# SCH_Emon.net
KiCad netlist of a schematic drawn in EasyEDA
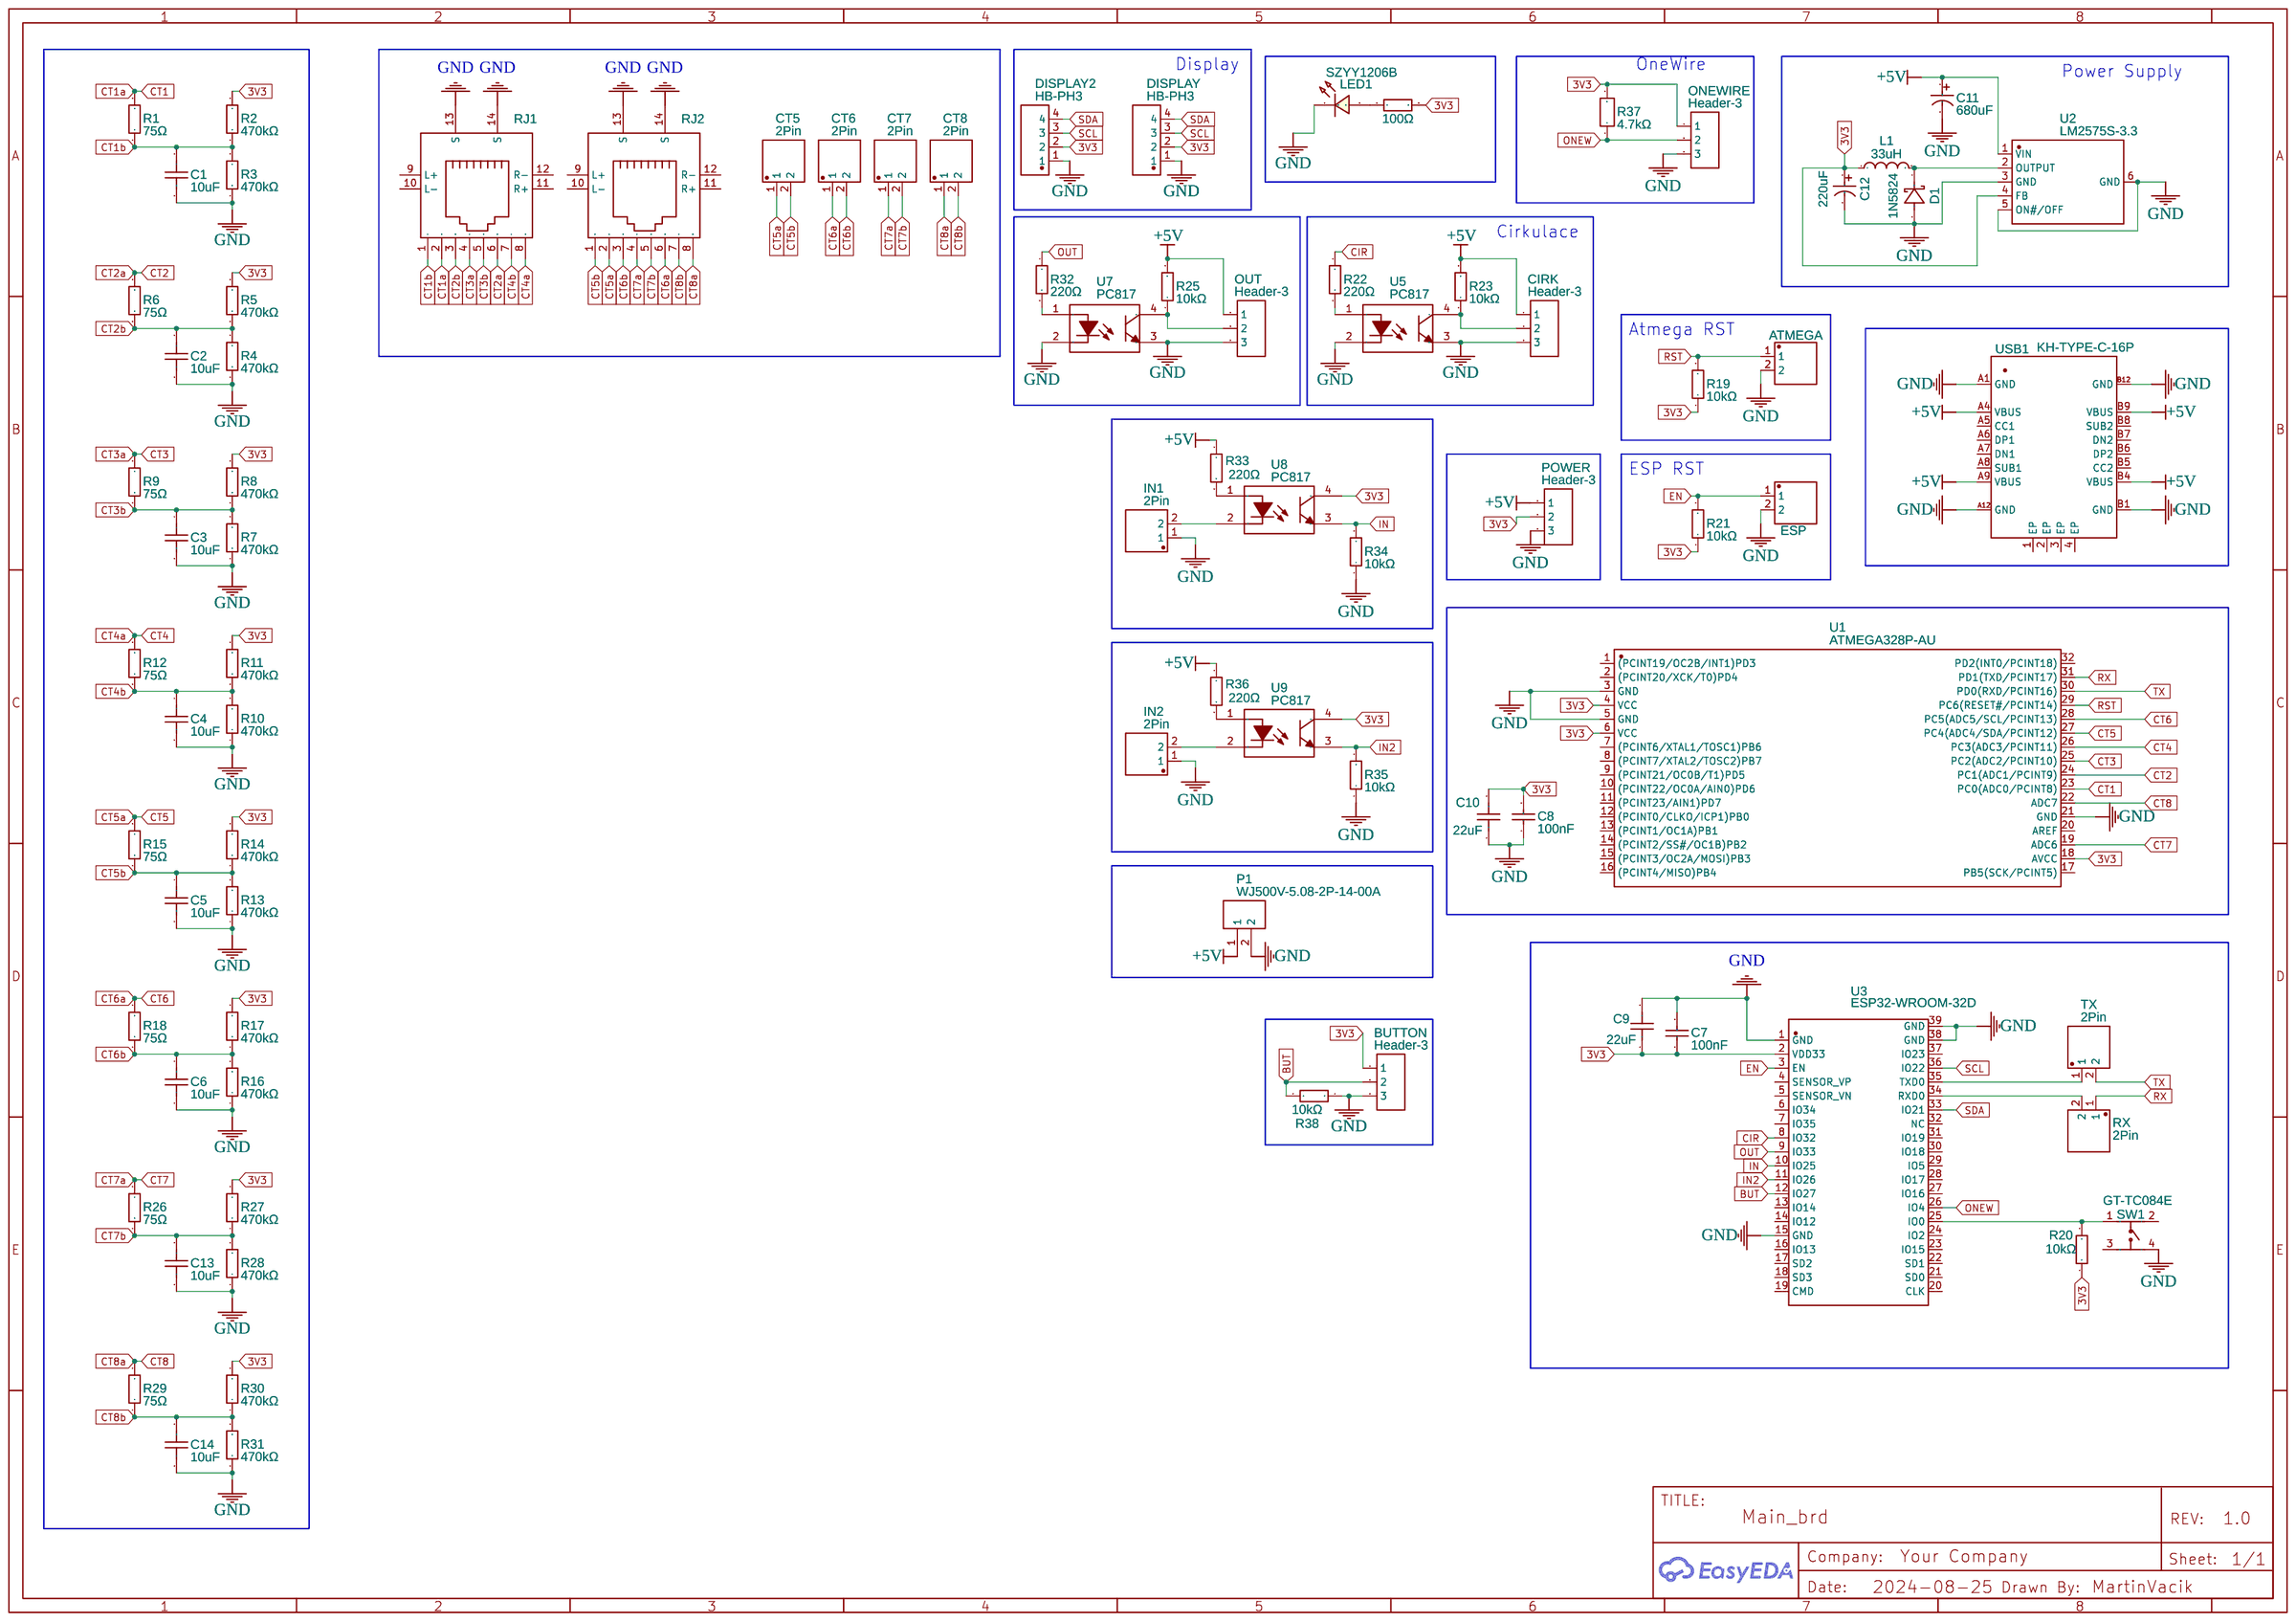
[diagram p0: schematic sheet]

(export (version "E")
  (design (tool "Eeschema 10.0.6"))
  (components
    (comp (ref "ATMEGA")
      (value "Atmega")
      (fields (field (name "Manufacturer Part") "B-2100S02P-A110") (field (name "Manufacturer") "Ckmtw(灿科盟)"))
      (libsource (lib "") (part "210S-1*2P L=11.6MMGold-plated black_2"))
    )
    (comp (ref "BUTTON")
      (value "Header-3")
      (fields (field (name "Manufacturer Part") "2.54-1*3P针") (field (name "Manufacturer") "BOOMELE(博穆精密)"))
      (libsource (lib "") (part "Header-Male-2.54_1x3_4"))
    )
    (comp (ref "C1")
      (value "10uF")
      (fields (field (name "Manufacturer Part") "1206B106K100NT") (field (name "Manufacturer") "FH(风华)"))
      (libsource (lib "") (part "1206B106K100NT"))
    )
    (comp (ref "C2")
      (value "10uF")
      (fields (field (name "Manufacturer Part") "1206B106K100NT") (field (name "Manufacturer") "FH(风华)"))
      (libsource (lib "") (part "1206B106K100NT"))
    )
    (comp (ref "C3")
      (value "10uF")
      (fields (field (name "Manufacturer Part") "1206B106K100NT") (field (name "Manufacturer") "FH(风华)"))
      (libsource (lib "") (part "1206B106K100NT"))
    )
    (comp (ref "C4")
      (value "10uF")
      (fields (field (name "Manufacturer Part") "1206B106K100NT") (field (name "Manufacturer") "FH(风华)"))
      (libsource (lib "") (part "1206B106K100NT"))
    )
    (comp (ref "C5")
      (value "10uF")
      (fields (field (name "Manufacturer Part") "1206B106K100NT") (field (name "Manufacturer") "FH(风华)"))
      (libsource (lib "") (part "1206B106K100NT"))
    )
    (comp (ref "C6")
      (value "10uF")
      (fields (field (name "Manufacturer Part") "1206B106K100NT") (field (name "Manufacturer") "FH(风华)"))
      (libsource (lib "") (part "1206B106K100NT"))
    )
    (comp (ref "C7")
      (value "100nF")
      (fields (field (name "Manufacturer Part") "1206B104K500NT") (field (name "Manufacturer") "FH(风华)"))
      (libsource (lib "") (part "1206B104K500NT"))
    )
    (comp (ref "C8")
      (value "100nF")
      (fields (field (name "Manufacturer Part") "1206B104K500NT") (field (name "Manufacturer") "FH(风华)"))
      (libsource (lib "") (part "1206B104K500NT"))
    )
    (comp (ref "C9")
      (value "22uF")
      (fields
        (field (name "Manufacturer Part") "CL31A226KOHNNNE")
        (field (name "Manufacturer") "SAMSUNG(三星)")
      )
      (libsource (lib "") (part "CL31A226KOHNNNE"))
    )
    (comp (ref "C10")
      (value "22uF")
      (fields
        (field (name "Manufacturer Part") "CL31A226KOHNNNE")
        (field (name "Manufacturer") "SAMSUNG(三星)")
      )
      (libsource (lib "") (part "CL31A226KOHNNNE"))
    )
    (comp (ref "C11")
      (value "680uF")
      (fields
        (field (name "Manufacturer Part") "GR687M025G17RR0VL4FP0")
        (field (name "Manufacturer") "CX(承兴)")
      )
      (libsource (lib "") (part "680uF 25V"))
    )
    (comp (ref "C12")
      (value "220uF")
      (fields
        (field (name "Manufacturer Part") "ZF227M016E07RR0VH4FP0")
        (field (name "Manufacturer") "CX(承兴)")
      )
      (libsource (lib "") (part "220uF 16V Black high frequency"))
    )
    (comp (ref "C13")
      (value "10uF")
      (fields (field (name "Manufacturer Part") "1206B106K100NT") (field (name "Manufacturer") "FH(风华)"))
      (libsource (lib "") (part "1206B106K100NT"))
    )
    (comp (ref "C14")
      (value "10uF")
      (fields (field (name "Manufacturer Part") "1206B106K100NT") (field (name "Manufacturer") "FH(风华)"))
      (libsource (lib "") (part "1206B106K100NT"))
    )
    (comp (ref "CIRK")
      (value "Header-3")
      (fields (field (name "Manufacturer Part") "2.54-1*3P针") (field (name "Manufacturer") "BOOMELE(博穆精密)"))
      (libsource (lib "") (part "Header-Male-2.54_1x3_3"))
    )
    (comp (ref "CT5")
      (value "2Pin")
      (fields (field (name "Manufacturer Part") "B-2100S02P-A110") (field (name "Manufacturer") "Ckmtw(灿科盟)"))
      (libsource (lib "") (part "210S-1*2P L=11.6MMGold-plated black_4"))
    )
    (comp (ref "CT6")
      (value "2Pin")
      (fields (field (name "Manufacturer Part") "B-2100S02P-A110") (field (name "Manufacturer") "Ckmtw(灿科盟)"))
      (libsource (lib "") (part "210S-1*2P L=11.6MMGold-plated black_4"))
    )
    (comp (ref "CT7")
      (value "2Pin")
      (fields (field (name "Manufacturer Part") "B-2100S02P-A110") (field (name "Manufacturer") "Ckmtw(灿科盟)"))
      (libsource (lib "") (part "210S-1*2P L=11.6MMGold-plated black_4"))
    )
    (comp (ref "CT8")
      (value "2Pin")
      (fields (field (name "Manufacturer Part") "B-2100S02P-A110") (field (name "Manufacturer") "Ckmtw(灿科盟)"))
      (libsource (lib "") (part "210S-1*2P L=11.6MMGold-plated black_4"))
    )
    (comp (ref "D1")
      (value "1N5824")
      (fields (field (name "Manufacturer") "FUXINSEMI(富芯森美)"))
      (libsource (lib "") (part "1N5824_C7503125"))
    )
    (comp (ref "DISPLAY")
      (value "HB-PH3")
      (fields
        (field (name "Manufacturer Part") "HB-PH3-25414PB2GOP")
        (field (name "Manufacturer") "HANBO(汉博)")
      )
      (libsource (lib "") (part "HB-PH3-25414PB2GOP"))
    )
    (comp (ref "DISPLAY2")
      (value "HB-PH3")
      (fields
        (field (name "Manufacturer Part") "HB-PH3-25414PB2GOP")
        (field (name "Manufacturer") "HANBO(汉博)")
      )
      (libsource (lib "") (part "HB-PH3-25414PB2GOP"))
    )
    (comp (ref "ESP")
      (value "ESP")
      (fields (field (name "Manufacturer Part") "B-2100S02P-A110") (field (name "Manufacturer") "Ckmtw(灿科盟)"))
      (libsource (lib "") (part "210S-1*2P L=11.6MMGold-plated black_3"))
    )
    (comp (ref "IN1")
      (value "2Pin")
      (fields (field (name "Manufacturer Part") "B-2100S02P-A110") (field (name "Manufacturer") "Ckmtw(灿科盟)"))
      (libsource (lib "") (part "210S-1*2P L=11.6MMGold-plated black_1"))
    )
    (comp (ref "IN2")
      (value "2Pin")
      (fields (field (name "Manufacturer Part") "B-2100S02P-A110") (field (name "Manufacturer") "Ckmtw(灿科盟)"))
      (libsource (lib "") (part "210S-1*2P L=11.6MMGold-plated black_1"))
    )
    (comp (ref "L1")
      (value "33uH")
      (fields (field (name "Manufacturer Part") "FXL0650-330-M") (field (name "Manufacturer") "cjiang(长江微电)"))
      (libsource (lib "") (part "FXL0650-330-M"))
    )
    (comp (ref "LED1")
      (value "SZYY1206B")
      (fields (field (name "Manufacturer") "yongyu(永裕光电)"))
      (libsource (lib "") (part "SZYY1206B"))
    )
    (comp (ref "ONEWIRE")
      (value "Header-3")
      (fields (field (name "Manufacturer Part") "2.54-1*3P针") (field (name "Manufacturer") "BOOMELE(博穆精密)"))
      (libsource (lib "") (part "Header-Male-2.54_1x3_1"))
    )
    (comp (ref "OUT")
      (value "Header-3")
      (fields (field (name "Manufacturer Part") "2.54-1*3P针") (field (name "Manufacturer") "BOOMELE(博穆精密)"))
      (libsource (lib "") (part "Header-Male-2.54_1x3"))
    )
    (comp (ref "P1")
      (value "WJ500V-5.08-2P-14-00A")
      (fields
        (field (name "Manufacturer Part") "WJ500V-5.08-2P")
        (field (name "Manufacturer") "KANGNEX(康奈克斯电气)")
      )
      (libsource (lib "") (part "WJ500V-5.08-2P-14-00A"))
    )
    (comp (ref "POWER")
      (value "Header-3")
      (fields (field (name "Manufacturer Part") "2.54-1*3P针") (field (name "Manufacturer") "BOOMELE(博穆精密)"))
      (libsource (lib "") (part "Header-Male-2.54_1x3_2"))
    )
    (comp (ref "R1")
      (value "75Ω")
      (fields
        (field (name "Manufacturer Part") "1206W4J0750T5E")
        (field (name "Manufacturer") "UNI-ROYAL(厚声)")
      )
      (libsource (lib "") (part "1206W4J0750T5E"))
    )
    (comp (ref "R2")
      (value "470kΩ")
      (fields
        (field (name "Manufacturer Part") "1206W4F4703T5E")
        (field (name "Manufacturer") "UNI-ROYAL(厚声)")
      )
      (libsource (lib "") (part "1206W4F4703T5E"))
    )
    (comp (ref "R3")
      (value "470kΩ")
      (fields
        (field (name "Manufacturer Part") "1206W4F4703T5E")
        (field (name "Manufacturer") "UNI-ROYAL(厚声)")
      )
      (libsource (lib "") (part "1206W4F4703T5E"))
    )
    (comp (ref "R4")
      (value "470kΩ")
      (fields
        (field (name "Manufacturer Part") "1206W4F4703T5E")
        (field (name "Manufacturer") "UNI-ROYAL(厚声)")
      )
      (libsource (lib "") (part "1206W4F4703T5E"))
    )
    (comp (ref "R5")
      (value "470kΩ")
      (fields
        (field (name "Manufacturer Part") "1206W4F4703T5E")
        (field (name "Manufacturer") "UNI-ROYAL(厚声)")
      )
      (libsource (lib "") (part "1206W4F4703T5E"))
    )
    (comp (ref "R6")
      (value "75Ω")
      (fields
        (field (name "Manufacturer Part") "1206W4J0750T5E")
        (field (name "Manufacturer") "UNI-ROYAL(厚声)")
      )
      (libsource (lib "") (part "1206W4J0750T5E"))
    )
    (comp (ref "R7")
      (value "470kΩ")
      (fields
        (field (name "Manufacturer Part") "1206W4F4703T5E")
        (field (name "Manufacturer") "UNI-ROYAL(厚声)")
      )
      (libsource (lib "") (part "1206W4F4703T5E"))
    )
    (comp (ref "R8")
      (value "470kΩ")
      (fields
        (field (name "Manufacturer Part") "1206W4F4703T5E")
        (field (name "Manufacturer") "UNI-ROYAL(厚声)")
      )
      (libsource (lib "") (part "1206W4F4703T5E"))
    )
    (comp (ref "R9")
      (value "75Ω")
      (fields
        (field (name "Manufacturer Part") "1206W4J0750T5E")
        (field (name "Manufacturer") "UNI-ROYAL(厚声)")
      )
      (libsource (lib "") (part "1206W4J0750T5E"))
    )
    (comp (ref "R10")
      (value "470kΩ")
      (fields
        (field (name "Manufacturer Part") "1206W4F4703T5E")
        (field (name "Manufacturer") "UNI-ROYAL(厚声)")
      )
      (libsource (lib "") (part "1206W4F4703T5E"))
    )
    (comp (ref "R11")
      (value "470kΩ")
      (fields
        (field (name "Manufacturer Part") "1206W4F4703T5E")
        (field (name "Manufacturer") "UNI-ROYAL(厚声)")
      )
      (libsource (lib "") (part "1206W4F4703T5E"))
    )
    (comp (ref "R12")
      (value "75Ω")
      (fields
        (field (name "Manufacturer Part") "1206W4J0750T5E")
        (field (name "Manufacturer") "UNI-ROYAL(厚声)")
      )
      (libsource (lib "") (part "1206W4J0750T5E"))
    )
    (comp (ref "R13")
      (value "470kΩ")
      (fields
        (field (name "Manufacturer Part") "1206W4F4703T5E")
        (field (name "Manufacturer") "UNI-ROYAL(厚声)")
      )
      (libsource (lib "") (part "1206W4F4703T5E"))
    )
    (comp (ref "R14")
      (value "470kΩ")
      (fields
        (field (name "Manufacturer Part") "1206W4F4703T5E")
        (field (name "Manufacturer") "UNI-ROYAL(厚声)")
      )
      (libsource (lib "") (part "1206W4F4703T5E"))
    )
    (comp (ref "R15")
      (value "75Ω")
      (fields
        (field (name "Manufacturer Part") "1206W4J0750T5E")
        (field (name "Manufacturer") "UNI-ROYAL(厚声)")
      )
      (libsource (lib "") (part "1206W4J0750T5E"))
    )
    (comp (ref "R16")
      (value "470kΩ")
      (fields
        (field (name "Manufacturer Part") "1206W4F4703T5E")
        (field (name "Manufacturer") "UNI-ROYAL(厚声)")
      )
      (libsource (lib "") (part "1206W4F4703T5E"))
    )
    (comp (ref "R17")
      (value "470kΩ")
      (fields
        (field (name "Manufacturer Part") "1206W4F4703T5E")
        (field (name "Manufacturer") "UNI-ROYAL(厚声)")
      )
      (libsource (lib "") (part "1206W4F4703T5E"))
    )
    (comp (ref "R18")
      (value "75Ω")
      (fields
        (field (name "Manufacturer Part") "1206W4J0750T5E")
        (field (name "Manufacturer") "UNI-ROYAL(厚声)")
      )
      (libsource (lib "") (part "1206W4J0750T5E"))
    )
    (comp (ref "R19")
      (value "10kΩ")
      (fields
        (field (name "Manufacturer Part") "1206W4F1002T5E")
        (field (name "Manufacturer") "UNI-ROYAL(厚声)")
      )
      (libsource (lib "") (part "1206W4F1002T5E"))
    )
    (comp (ref "R20")
      (value "10kΩ")
      (fields
        (field (name "Manufacturer Part") "1206W4F1002T5E")
        (field (name "Manufacturer") "UNI-ROYAL(厚声)")
      )
      (libsource (lib "") (part "1206W4F1002T5E"))
    )
    (comp (ref "R21")
      (value "10kΩ")
      (fields
        (field (name "Manufacturer Part") "1206W4F1002T5E")
        (field (name "Manufacturer") "UNI-ROYAL(厚声)")
      )
      (libsource (lib "") (part "1206W4F1002T5E"))
    )
    (comp (ref "R22")
      (value "220Ω")
      (fields
        (field (name "Manufacturer Part") "1206W4J0221T5E")
        (field (name "Manufacturer") "UNI-ROYAL(厚声)")
      )
      (libsource (lib "") (part "1206W4J0221T5E"))
    )
    (comp (ref "R23")
      (value "10kΩ")
      (fields
        (field (name "Manufacturer Part") "1206W4F1002T5E")
        (field (name "Manufacturer") "UNI-ROYAL(厚声)")
      )
      (libsource (lib "") (part "1206W4F1002T5E"))
    )
    (comp (ref "R24")
      (value "100Ω")
      (fields
        (field (name "Manufacturer Part") "1206W4F1000T5E")
        (field (name "Manufacturer") "UNI-ROYAL(厚声)")
      )
      (libsource (lib "") (part "1206W4F1000T5E"))
    )
    (comp (ref "R25")
      (value "10kΩ")
      (fields
        (field (name "Manufacturer Part") "1206W4F1002T5E")
        (field (name "Manufacturer") "UNI-ROYAL(厚声)")
      )
      (libsource (lib "") (part "1206W4F1002T5E"))
    )
    (comp (ref "R26")
      (value "75Ω")
      (fields
        (field (name "Manufacturer Part") "1206W4J0750T5E")
        (field (name "Manufacturer") "UNI-ROYAL(厚声)")
      )
      (libsource (lib "") (part "1206W4J0750T5E"))
    )
    (comp (ref "R27")
      (value "470kΩ")
      (fields
        (field (name "Manufacturer Part") "1206W4F4703T5E")
        (field (name "Manufacturer") "UNI-ROYAL(厚声)")
      )
      (libsource (lib "") (part "1206W4F4703T5E"))
    )
    (comp (ref "R28")
      (value "470kΩ")
      (fields
        (field (name "Manufacturer Part") "1206W4F4703T5E")
        (field (name "Manufacturer") "UNI-ROYAL(厚声)")
      )
      (libsource (lib "") (part "1206W4F4703T5E"))
    )
    (comp (ref "R29")
      (value "75Ω")
      (fields
        (field (name "Manufacturer Part") "1206W4J0750T5E")
        (field (name "Manufacturer") "UNI-ROYAL(厚声)")
      )
      (libsource (lib "") (part "1206W4J0750T5E"))
    )
    (comp (ref "R30")
      (value "470kΩ")
      (fields
        (field (name "Manufacturer Part") "1206W4F4703T5E")
        (field (name "Manufacturer") "UNI-ROYAL(厚声)")
      )
      (libsource (lib "") (part "1206W4F4703T5E"))
    )
    (comp (ref "R31")
      (value "470kΩ")
      (fields
        (field (name "Manufacturer Part") "1206W4F4703T5E")
        (field (name "Manufacturer") "UNI-ROYAL(厚声)")
      )
      (libsource (lib "") (part "1206W4F4703T5E"))
    )
    (comp (ref "R32")
      (value "220Ω")
      (fields
        (field (name "Manufacturer Part") "1206W4J0221T5E")
        (field (name "Manufacturer") "UNI-ROYAL(厚声)")
      )
      (libsource (lib "") (part "1206W4J0221T5E"))
    )
    (comp (ref "R33")
      (value "220Ω")
      (fields
        (field (name "Manufacturer Part") "1206W4J0221T5E")
        (field (name "Manufacturer") "UNI-ROYAL(厚声)")
      )
      (libsource (lib "") (part "1206W4J0221T5E"))
    )
    (comp (ref "R34")
      (value "10kΩ")
      (fields
        (field (name "Manufacturer Part") "1206W4F1002T5E")
        (field (name "Manufacturer") "UNI-ROYAL(厚声)")
      )
      (libsource (lib "") (part "1206W4F1002T5E"))
    )
    (comp (ref "R35")
      (value "10kΩ")
      (fields
        (field (name "Manufacturer Part") "1206W4F1002T5E")
        (field (name "Manufacturer") "UNI-ROYAL(厚声)")
      )
      (libsource (lib "") (part "1206W4F1002T5E"))
    )
    (comp (ref "R36")
      (value "220Ω")
      (fields
        (field (name "Manufacturer Part") "1206W4J0221T5E")
        (field (name "Manufacturer") "UNI-ROYAL(厚声)")
      )
      (libsource (lib "") (part "1206W4J0221T5E"))
    )
    (comp (ref "R37")
      (value "4.7kΩ")
      (fields (field (name "Manufacturer Part") "FRC1206J472 TS") (field (name "Manufacturer") "FOJAN(富捷)"))
      (libsource (lib "") (part "FRC1206J472 TS"))
    )
    (comp (ref "R38")
      (value "10kΩ")
      (fields
        (field (name "Manufacturer Part") "1206W4F1002T5E")
        (field (name "Manufacturer") "UNI-ROYAL(厚声)")
      )
      (libsource (lib "") (part "1206W4F1002T5E_1"))
    )
    (comp (ref "RJ1")
      (value "R-RJ45R08P-C000")
      (fields (field (name "Manufacturer") "Ckmtw(灿科盟)"))
      (libsource (lib "") (part "R-RJ45R08P-C000"))
    )
    (comp (ref "RJ2")
      (value "R-RJ45R08P-C000")
      (fields (field (name "Manufacturer") "Ckmtw(灿科盟)"))
      (libsource (lib "") (part "R-RJ45R08P-C000"))
    )
    (comp (ref "RX")
      (value "2Pin")
      (fields (field (name "Manufacturer Part") "B-2100S02P-A110") (field (name "Manufacturer") "Ckmtw(灿科盟)"))
      (libsource (lib "") (part "210S-1*2P L=11.6MMGold-plated black_5"))
    )
    (comp (ref "SW1")
      (value "GT-TC084E")
      (fields
        (field (name "Manufacturer Part") "GT-TC084E-H017-L5")
        (field (name "Manufacturer") "G-Switch(品赞)")
      )
      (libsource (lib "") (part "GT-TC084E-H017-L5"))
    )
    (comp (ref "TX")
      (value "2Pin")
      (fields (field (name "Manufacturer Part") "B-2100S02P-A110") (field (name "Manufacturer") "Ckmtw(灿科盟)"))
      (libsource (lib "") (part "210S-1*2P L=11.6MMGold-plated black"))
    )
    (comp (ref "U1")
      (value "ATMEGA328P-AU")
      (fields (field (name "Manufacturer") "MICROCHIP(美国微芯)"))
      (libsource (lib "") (part "ATMEGA328P-AU"))
    )
    (comp (ref "U2")
      (value "LM2575S-3.3")
      (fields (field (name "Manufacturer") "UMW(友台半导体)"))
      (libsource (lib "") (part "LM2575S-3.3_C347404"))
    )
    (comp (ref "U3")
      (value "ESP32-WROOM-32D")
      (fields
        (field (name "Manufacturer Part") "ESP32-WROOM-32D-N4")
        (field (name "Manufacturer") "ESPRESSIF(乐鑫)")
      )
      (libsource (lib "") (part "ESP32-WROOM-32D"))
    )
    (comp (ref "U5")
      (value "PC817")
      (fields (field (name "Manufacturer Part") "PC817X2CSP9F") (field (name "Manufacturer") "SHARP(夏普)"))
      (libsource (lib "") (part "PC817X2CSP9F"))
    )
    (comp (ref "U7")
      (value "PC817")
      (fields (field (name "Manufacturer Part") "PC817X2CSP9F") (field (name "Manufacturer") "SHARP(夏普)"))
      (libsource (lib "") (part "PC817X2CSP9F"))
    )
    (comp (ref "U8")
      (value "PC817")
      (fields (field (name "Manufacturer Part") "PC817X2CSP9F") (field (name "Manufacturer") "SHARP(夏普)"))
      (libsource (lib "") (part "PC817X2CSP9F"))
    )
    (comp (ref "U9")
      (value "PC817")
      (fields (field (name "Manufacturer Part") "PC817X2CSP9F") (field (name "Manufacturer") "SHARP(夏普)"))
      (libsource (lib "") (part "PC817X2CSP9F"))
    )
    (comp (ref "USB1")
      (value "KH-TYPE-C-16P")
      (fields (field (name "Manufacturer") "kinghelm(金航标)"))
      (libsource (lib "") (part "KH-TYPE-C-16P"))
    )
  )
  (nets
    (net (code "1") (name "+5V") (class "Default")
      (node (ref "C11") (pin "1") (pinfunction "1_1") (pintype "input"))
      (node (ref "CIRK") (pin "1") (pinfunction "1_1") (pintype "input"))
      (node (ref "OUT") (pin "1") (pinfunction "1_1") (pintype "input"))
      (node (ref "P1") (pin "1") (pinfunction "1_1") (pintype "unspecified"))
      (node (ref "POWER") (pin "1") (pinfunction "1_1") (pintype "input"))
      (node (ref "R23") (pin "2") (pinfunction "2_2") (pintype "input"))
      (node (ref "R25") (pin "2") (pinfunction "2_2") (pintype "input"))
      (node (ref "R33") (pin "1") (pinfunction "1_1") (pintype "input"))
      (node (ref "R36") (pin "1") (pinfunction "1_1") (pintype "input"))
      (node (ref "U2") (pin "1") (pinfunction "VIN_1") (pintype "unspecified"))
      (node (ref "USB1") (pin "A4") (pinfunction "VBUS_A4") (pintype "unspecified"))
      (node (ref "USB1") (pin "A9") (pinfunction "VBUS_A9") (pintype "unspecified"))
      (node (ref "USB1") (pin "B4") (pinfunction "VBUS_B4") (pintype "unspecified"))
      (node (ref "USB1") (pin "B9") (pinfunction "VBUS_B9") (pintype "unspecified"))
    )
    (net (code "2") (name "3V3") (class "Default")
      (node (ref "BUTTON") (pin "1") (pinfunction "1_1") (pintype "input"))
      (node (ref "C10") (pin "2") (pinfunction "2_2") (pintype "unspecified"))
      (node (ref "C12") (pin "1") (pinfunction "1_1") (pintype "input"))
      (node (ref "C7") (pin "1") (pinfunction "1_1") (pintype "input"))
      (node (ref "C8") (pin "2") (pinfunction "2_2") (pintype "input"))
      (node (ref "C9") (pin "1") (pinfunction "1_1") (pintype "unspecified"))
      (node (ref "DISPLAY") (pin "2") (pinfunction "2_2") (pintype "unspecified"))
      (node (ref "DISPLAY2") (pin "2") (pinfunction "2_2") (pintype "unspecified"))
      (node (ref "L1") (pin "1") (pinfunction "1_1") (pintype "unspecified"))
      (node (ref "ONEWIRE") (pin "1") (pinfunction "1_1") (pintype "input"))
      (node (ref "POWER") (pin "2") (pinfunction "2_2") (pintype "input"))
      (node (ref "R11") (pin "2") (pinfunction "2_2") (pintype "input"))
      (node (ref "R14") (pin "2") (pinfunction "2_2") (pintype "input"))
      (node (ref "R17") (pin "2") (pinfunction "2_2") (pintype "input"))
      (node (ref "R19") (pin "1") (pinfunction "1_1") (pintype "input"))
      (node (ref "R2") (pin "2") (pinfunction "2_2") (pintype "input"))
      (node (ref "R20") (pin "1") (pinfunction "1_1") (pintype "input"))
      (node (ref "R21") (pin "1") (pinfunction "1_1") (pintype "input"))
      (node (ref "R24") (pin "2") (pinfunction "2_2") (pintype "input"))
      (node (ref "R27") (pin "2") (pinfunction "2_2") (pintype "input"))
      (node (ref "R30") (pin "2") (pinfunction "2_2") (pintype "input"))
      (node (ref "R37") (pin "2") (pinfunction "2_2") (pintype "unspecified"))
      (node (ref "R5") (pin "2") (pinfunction "2_2") (pintype "input"))
      (node (ref "R8") (pin "2") (pinfunction "2_2") (pintype "input"))
      (node (ref "U1") (pin "18") (pinfunction "AVCC_18") (pintype "unspecified"))
      (node (ref "U1") (pin "4") (pinfunction "VCC_4") (pintype "unspecified"))
      (node (ref "U1") (pin "6") (pinfunction "VCC_6") (pintype "unspecified"))
      (node (ref "U2") (pin "4") (pinfunction "FB_4") (pintype "unspecified"))
      (node (ref "U3") (pin "2") (pinfunction "VDD33_2") (pintype "unspecified"))
      (node (ref "U8") (pin "4") (pinfunction "4_4") (pintype "unspecified"))
      (node (ref "U9") (pin "4") (pinfunction "4_4") (pintype "unspecified"))
    )
    (net (code "3") (name "BUT") (class "Default")
      (node (ref "BUTTON") (pin "2") (pinfunction "2_2") (pintype "input"))
      (node (ref "R38") (pin "2") (pinfunction "2_2") (pintype "input"))
      (node (ref "U3") (pin "12") (pinfunction "IO27_12") (pintype "unspecified"))
    )
    (net (code "4") (name "CIR") (class "Default")
      (node (ref "R22") (pin "1") (pinfunction "1_1") (pintype "input"))
      (node (ref "U3") (pin "8") (pinfunction "IO32_8") (pintype "unspecified"))
    )
    (net (code "5") (name "CT1") (class "Default")
      (node (ref "R1") (pin "2") (pinfunction "2_2") (pintype "input"))
      (node (ref "RJ1") (pin "2") (pinfunction "2_2") (pintype "unspecified"))
      (node (ref "U1") (pin "23") (pinfunction "PC0(ADC0/PCINT8)_23") (pintype "unspecified"))
    )
    (net (code "6") (name "CT1b") (class "Default")
      (node (ref "C1") (pin "1") (pinfunction "1_1") (pintype "unspecified"))
      (node (ref "R1") (pin "1") (pinfunction "1_1") (pintype "input"))
      (node (ref "R2") (pin "1") (pinfunction "1_1") (pintype "input"))
      (node (ref "R3") (pin "2") (pinfunction "2_2") (pintype "input"))
      (node (ref "RJ1") (pin "1") (pinfunction "1_1") (pintype "unspecified"))
    )
    (net (code "7") (name "CT2") (class "Default")
      (node (ref "R6") (pin "2") (pinfunction "2_2") (pintype "input"))
      (node (ref "RJ1") (pin "6") (pinfunction "6_6") (pintype "unspecified"))
      (node (ref "U1") (pin "24") (pinfunction "PC1(ADC1/PCINT9)_24") (pintype "unspecified"))
    )
    (net (code "8") (name "CT2b") (class "Default")
      (node (ref "C2") (pin "1") (pinfunction "1_1") (pintype "unspecified"))
      (node (ref "R4") (pin "2") (pinfunction "2_2") (pintype "input"))
      (node (ref "R5") (pin "1") (pinfunction "1_1") (pintype "input"))
      (node (ref "R6") (pin "1") (pinfunction "1_1") (pintype "input"))
      (node (ref "RJ1") (pin "3") (pinfunction "3_3") (pintype "unspecified"))
    )
    (net (code "9") (name "CT3") (class "Default")
      (node (ref "R9") (pin "2") (pinfunction "2_2") (pintype "input"))
      (node (ref "RJ1") (pin "4") (pinfunction "4_4") (pintype "unspecified"))
      (node (ref "U1") (pin "25") (pinfunction "PC2(ADC2/PCINT10)_25") (pintype "unspecified"))
    )
    (net (code "10") (name "CT3b") (class "Default")
      (node (ref "C3") (pin "1") (pinfunction "1_1") (pintype "unspecified"))
      (node (ref "R7") (pin "2") (pinfunction "2_2") (pintype "input"))
      (node (ref "R8") (pin "1") (pinfunction "1_1") (pintype "input"))
      (node (ref "R9") (pin "1") (pinfunction "1_1") (pintype "input"))
      (node (ref "RJ1") (pin "5") (pinfunction "5_5") (pintype "unspecified"))
    )
    (net (code "11") (name "CT4") (class "Default")
      (node (ref "R12") (pin "2") (pinfunction "2_2") (pintype "input"))
      (node (ref "RJ1") (pin "8") (pinfunction "8_8") (pintype "unspecified"))
      (node (ref "U1") (pin "26") (pinfunction "PC3(ADC3/PCINT11)_26") (pintype "unspecified"))
    )
    (net (code "12") (name "CT4b") (class "Default")
      (node (ref "C4") (pin "1") (pinfunction "1_1") (pintype "unspecified"))
      (node (ref "R10") (pin "2") (pinfunction "2_2") (pintype "input"))
      (node (ref "R11") (pin "1") (pinfunction "1_1") (pintype "input"))
      (node (ref "R12") (pin "1") (pinfunction "1_1") (pintype "input"))
      (node (ref "RJ1") (pin "7") (pinfunction "7_7") (pintype "unspecified"))
    )
    (net (code "13") (name "CT5") (class "Default")
      (node (ref "CT5") (pin "1") (pinfunction "1_1") (pintype "unspecified"))
      (node (ref "R15") (pin "2") (pinfunction "2_2") (pintype "input"))
      (node (ref "RJ2") (pin "2") (pinfunction "2_2") (pintype "unspecified"))
      (node (ref "U1") (pin "27") (pinfunction "PC4(ADC4/SDA/PCINT12)_27") (pintype "unspecified"))
    )
    (net (code "14") (name "CT5b") (class "Default")
      (node (ref "C5") (pin "1") (pinfunction "1_1") (pintype "unspecified"))
      (node (ref "CT5") (pin "2") (pinfunction "2_2") (pintype "unspecified"))
      (node (ref "R13") (pin "2") (pinfunction "2_2") (pintype "input"))
      (node (ref "R14") (pin "1") (pinfunction "1_1") (pintype "input"))
      (node (ref "R15") (pin "1") (pinfunction "1_1") (pintype "input"))
      (node (ref "RJ2") (pin "1") (pinfunction "1_1") (pintype "unspecified"))
    )
    (net (code "15") (name "CT6") (class "Default")
      (node (ref "CT6") (pin "1") (pinfunction "1_1") (pintype "unspecified"))
      (node (ref "R18") (pin "2") (pinfunction "2_2") (pintype "input"))
      (node (ref "RJ2") (pin "6") (pinfunction "6_6") (pintype "unspecified"))
      (node (ref "U1") (pin "28") (pinfunction "PC5(ADC5/SCL/PCINT13)_28") (pintype "unspecified"))
    )
    (net (code "16") (name "CT6b") (class "Default")
      (node (ref "C6") (pin "1") (pinfunction "1_1") (pintype "unspecified"))
      (node (ref "CT6") (pin "2") (pinfunction "2_2") (pintype "unspecified"))
      (node (ref "R16") (pin "2") (pinfunction "2_2") (pintype "input"))
      (node (ref "R17") (pin "1") (pinfunction "1_1") (pintype "input"))
      (node (ref "R18") (pin "1") (pinfunction "1_1") (pintype "input"))
      (node (ref "RJ2") (pin "3") (pinfunction "3_3") (pintype "unspecified"))
    )
    (net (code "17") (name "CT7") (class "Default")
      (node (ref "CT7") (pin "1") (pinfunction "1_1") (pintype "unspecified"))
      (node (ref "R26") (pin "2") (pinfunction "2_2") (pintype "input"))
      (node (ref "RJ2") (pin "4") (pinfunction "4_4") (pintype "unspecified"))
      (node (ref "U1") (pin "19") (pinfunction "ADC6_19") (pintype "unspecified"))
    )
    (net (code "18") (name "CT7b") (class "Default")
      (node (ref "C13") (pin "1") (pinfunction "1_1") (pintype "unspecified"))
      (node (ref "CT7") (pin "2") (pinfunction "2_2") (pintype "unspecified"))
      (node (ref "R26") (pin "1") (pinfunction "1_1") (pintype "input"))
      (node (ref "R27") (pin "1") (pinfunction "1_1") (pintype "input"))
      (node (ref "R28") (pin "2") (pinfunction "2_2") (pintype "input"))
      (node (ref "RJ2") (pin "5") (pinfunction "5_5") (pintype "unspecified"))
    )
    (net (code "19") (name "CT8") (class "Default")
      (node (ref "CT8") (pin "1") (pinfunction "1_1") (pintype "unspecified"))
      (node (ref "R29") (pin "2") (pinfunction "2_2") (pintype "input"))
      (node (ref "RJ2") (pin "8") (pinfunction "8_8") (pintype "unspecified"))
      (node (ref "U1") (pin "22") (pinfunction "ADC7_22") (pintype "unspecified"))
    )
    (net (code "20") (name "CT8b") (class "Default")
      (node (ref "C14") (pin "1") (pinfunction "1_1") (pintype "unspecified"))
      (node (ref "CT8") (pin "2") (pinfunction "2_2") (pintype "unspecified"))
      (node (ref "R29") (pin "1") (pinfunction "1_1") (pintype "input"))
      (node (ref "R30") (pin "1") (pinfunction "1_1") (pintype "input"))
      (node (ref "R31") (pin "2") (pinfunction "2_2") (pintype "input"))
      (node (ref "RJ2") (pin "7") (pinfunction "7_7") (pintype "unspecified"))
    )
    (net (code "21") (name "EN") (class "Default")
      (node (ref "ESP") (pin "1") (pinfunction "1_1") (pintype "unspecified"))
      (node (ref "R21") (pin "2") (pinfunction "2_2") (pintype "input"))
      (node (ref "U3") (pin "3") (pinfunction "EN_3") (pintype "unspecified"))
    )
    (net (code "22") (name "GND") (class "Default")
      (node (ref "ATMEGA") (pin "2") (pinfunction "2_2") (pintype "unspecified"))
      (node (ref "BUTTON") (pin "3") (pinfunction "3_3") (pintype "input"))
      (node (ref "C1") (pin "2") (pinfunction "2_2") (pintype "unspecified"))
      (node (ref "C10") (pin "1") (pinfunction "1_1") (pintype "unspecified"))
      (node (ref "C11") (pin "2") (pinfunction "2_2") (pintype "input"))
      (node (ref "C12") (pin "2") (pinfunction "2_2") (pintype "input"))
      (node (ref "C13") (pin "2") (pinfunction "2_2") (pintype "unspecified"))
      (node (ref "C14") (pin "2") (pinfunction "2_2") (pintype "unspecified"))
      (node (ref "C2") (pin "2") (pinfunction "2_2") (pintype "unspecified"))
      (node (ref "C3") (pin "2") (pinfunction "2_2") (pintype "unspecified"))
      (node (ref "C4") (pin "2") (pinfunction "2_2") (pintype "unspecified"))
      (node (ref "C5") (pin "2") (pinfunction "2_2") (pintype "unspecified"))
      (node (ref "C6") (pin "2") (pinfunction "2_2") (pintype "unspecified"))
      (node (ref "C7") (pin "2") (pinfunction "2_2") (pintype "input"))
      (node (ref "C8") (pin "1") (pinfunction "1_1") (pintype "input"))
      (node (ref "C9") (pin "2") (pinfunction "2_2") (pintype "unspecified"))
      (node (ref "CIRK") (pin "3") (pinfunction "3_3") (pintype "input"))
      (node (ref "D1") (pin "2") (pinfunction "A_2") (pintype "unspecified"))
      (node (ref "DISPLAY") (pin "1") (pinfunction "1_1") (pintype "unspecified"))
      (node (ref "DISPLAY2") (pin "1") (pinfunction "1_1") (pintype "unspecified"))
      (node (ref "ESP") (pin "2") (pinfunction "2_2") (pintype "unspecified"))
      (node (ref "IN1") (pin "1") (pinfunction "1_1") (pintype "unspecified"))
      (node (ref "IN2") (pin "1") (pinfunction "1_1") (pintype "unspecified"))
      (node (ref "LED1") (pin "1") (pinfunction "1_1") (pintype "unspecified"))
      (node (ref "ONEWIRE") (pin "3") (pinfunction "3_3") (pintype "input"))
      (node (ref "OUT") (pin "3") (pinfunction "3_3") (pintype "input"))
      (node (ref "P1") (pin "2") (pinfunction "2_2") (pintype "unspecified"))
      (node (ref "POWER") (pin "3") (pinfunction "3_3") (pintype "input"))
      (node (ref "R10") (pin "1") (pinfunction "1_1") (pintype "input"))
      (node (ref "R13") (pin "1") (pinfunction "1_1") (pintype "input"))
      (node (ref "R16") (pin "1") (pinfunction "1_1") (pintype "input"))
      (node (ref "R28") (pin "1") (pinfunction "1_1") (pintype "input"))
      (node (ref "R3") (pin "1") (pinfunction "1_1") (pintype "input"))
      (node (ref "R31") (pin "1") (pinfunction "1_1") (pintype "input"))
      (node (ref "R34") (pin "1") (pinfunction "1_1") (pintype "input"))
      (node (ref "R35") (pin "1") (pinfunction "1_1") (pintype "input"))
      (node (ref "R38") (pin "1") (pinfunction "1_1") (pintype "input"))
      (node (ref "R4") (pin "1") (pinfunction "1_1") (pintype "input"))
      (node (ref "R7") (pin "1") (pinfunction "1_1") (pintype "input"))
      (node (ref "RJ1") (pin "13") (pinfunction "S_13") (pintype "unspecified"))
      (node (ref "RJ1") (pin "14") (pinfunction "S_14") (pintype "unspecified"))
      (node (ref "RJ2") (pin "13") (pinfunction "S_13") (pintype "unspecified"))
      (node (ref "RJ2") (pin "14") (pinfunction "S_14") (pintype "unspecified"))
      (node (ref "SW1") (pin "4") (pinfunction "4_4") (pintype "unspecified"))
      (node (ref "U1") (pin "21") (pinfunction "GND_21") (pintype "unspecified"))
      (node (ref "U1") (pin "3") (pinfunction "GND_3") (pintype "unspecified"))
      (node (ref "U1") (pin "5") (pinfunction "GND_5") (pintype "unspecified"))
      (node (ref "U2") (pin "3") (pinfunction "GND_3") (pintype "unspecified"))
      (node (ref "U2") (pin "5") (pinfunction "ON#/OFF_5") (pintype "unspecified"))
      (node (ref "U2") (pin "6") (pinfunction "GND_6") (pintype "unspecified"))
      (node (ref "U3") (pin "1") (pinfunction "GND_1") (pintype "unspecified"))
      (node (ref "U3") (pin "15") (pinfunction "GND_15") (pintype "unspecified"))
      (node (ref "U3") (pin "38") (pinfunction "GND_38") (pintype "unspecified"))
      (node (ref "U3") (pin "39") (pinfunction "GND_39") (pintype "unspecified"))
      (node (ref "U5") (pin "2") (pinfunction "2_2") (pintype "unspecified"))
      (node (ref "U5") (pin "3") (pinfunction "3_3") (pintype "unspecified"))
      (node (ref "U7") (pin "2") (pinfunction "2_2") (pintype "unspecified"))
      (node (ref "U7") (pin "3") (pinfunction "3_3") (pintype "unspecified"))
      (node (ref "USB1") (pin "A1") (pinfunction "GND_A1") (pintype "unspecified"))
      (node (ref "USB1") (pin "A12") (pinfunction "GND_A12") (pintype "unspecified"))
      (node (ref "USB1") (pin "B1") (pinfunction "GND_B1") (pintype "unspecified"))
      (node (ref "USB1") (pin "B12") (pinfunction "GND_B12") (pintype "unspecified"))
    )
    (net (code "23") (name "IN") (class "Default")
      (node (ref "R34") (pin "2") (pinfunction "2_2") (pintype "input"))
      (node (ref "U3") (pin "10") (pinfunction "IO25_10") (pintype "unspecified"))
      (node (ref "U8") (pin "3") (pinfunction "3_3") (pintype "unspecified"))
    )
    (net (code "24") (name "IN2") (class "Default")
      (node (ref "R35") (pin "2") (pinfunction "2_2") (pintype "input"))
      (node (ref "U3") (pin "11") (pinfunction "IO26_11") (pintype "unspecified"))
      (node (ref "U9") (pin "3") (pinfunction "3_3") (pintype "unspecified"))
    )
    (net (code "25") (name "Net-(CIRK-Pad2)") (class "Default")
      (node (ref "CIRK") (pin "2") (pinfunction "2_2") (pintype "input"))
      (node (ref "R23") (pin "1") (pinfunction "1_1") (pintype "input"))
      (node (ref "U5") (pin "4") (pinfunction "4_4") (pintype "unspecified"))
    )
    (net (code "26") (name "Net-(D1-K)") (class "Default")
      (node (ref "D1") (pin "1") (pinfunction "K_1") (pintype "unspecified"))
      (node (ref "L1") (pin "2") (pinfunction "2_2") (pintype "unspecified"))
      (node (ref "U2") (pin "2") (pinfunction "OUTPUT_2") (pintype "unspecified"))
    )
    (net (code "27") (name "Net-(IN1-Pad2)") (class "Default")
      (node (ref "IN1") (pin "2") (pinfunction "2_2") (pintype "unspecified"))
      (node (ref "U8") (pin "2") (pinfunction "2_2") (pintype "unspecified"))
    )
    (net (code "28") (name "Net-(IN2-Pad2)") (class "Default")
      (node (ref "IN2") (pin "2") (pinfunction "2_2") (pintype "unspecified"))
      (node (ref "U9") (pin "2") (pinfunction "2_2") (pintype "unspecified"))
    )
    (net (code "29") (name "Net-(LED1-Pad2)") (class "Default")
      (node (ref "LED1") (pin "2") (pinfunction "2_2") (pintype "unspecified"))
      (node (ref "R24") (pin "1") (pinfunction "1_1") (pintype "input"))
    )
    (net (code "30") (name "Net-(OUT-Pad2)") (class "Default")
      (node (ref "OUT") (pin "2") (pinfunction "2_2") (pintype "input"))
      (node (ref "R25") (pin "1") (pinfunction "1_1") (pintype "input"))
      (node (ref "U7") (pin "4") (pinfunction "4_4") (pintype "unspecified"))
    )
    (net (code "31") (name "Net-(R22-Pad2)") (class "Default")
      (node (ref "R22") (pin "2") (pinfunction "2_2") (pintype "input"))
      (node (ref "U5") (pin "1") (pinfunction "1_1") (pintype "unspecified"))
    )
    (net (code "32") (name "Net-(R32-Pad2)") (class "Default")
      (node (ref "R32") (pin "2") (pinfunction "2_2") (pintype "input"))
      (node (ref "U7") (pin "1") (pinfunction "1_1") (pintype "unspecified"))
    )
    (net (code "33") (name "Net-(R33-Pad2)") (class "Default")
      (node (ref "R33") (pin "2") (pinfunction "2_2") (pintype "input"))
      (node (ref "U8") (pin "1") (pinfunction "1_1") (pintype "unspecified"))
    )
    (net (code "34") (name "Net-(R36-Pad2)") (class "Default")
      (node (ref "R36") (pin "2") (pinfunction "2_2") (pintype "input"))
      (node (ref "U9") (pin "1") (pinfunction "1_1") (pintype "unspecified"))
    )
    (net (code "35") (name "Net-(U3-IO0)") (class "Default")
      (node (ref "R20") (pin "2") (pinfunction "2_2") (pintype "input"))
      (node (ref "SW1") (pin "1") (pinfunction "1_1") (pintype "unspecified"))
      (node (ref "U3") (pin "25") (pinfunction "IO0_25") (pintype "unspecified"))
    )
    (net (code "36") (name "Net-(U3-RXD0)") (class "Default")
      (node (ref "RX") (pin "2") (pinfunction "2_2") (pintype "unspecified"))
      (node (ref "U3") (pin "34") (pinfunction "RXD0_34") (pintype "unspecified"))
    )
    (net (code "37") (name "Net-(U3-TXD0)") (class "Default")
      (node (ref "TX") (pin "1") (pinfunction "1_1") (pintype "unspecified"))
      (node (ref "U3") (pin "35") (pinfunction "TXD0_35") (pintype "unspecified"))
    )
    (net (code "38") (name "ONEW") (class "Default")
      (node (ref "ONEWIRE") (pin "2") (pinfunction "2_2") (pintype "input"))
      (node (ref "R37") (pin "1") (pinfunction "1_1") (pintype "unspecified"))
      (node (ref "U3") (pin "26") (pinfunction "IO4_26") (pintype "unspecified"))
    )
    (net (code "39") (name "OUT") (class "Default")
      (node (ref "R32") (pin "1") (pinfunction "1_1") (pintype "input"))
      (node (ref "U3") (pin "9") (pinfunction "IO33_9") (pintype "unspecified"))
    )
    (net (code "40") (name "RST") (class "Default")
      (node (ref "ATMEGA") (pin "1") (pinfunction "1_1") (pintype "unspecified"))
      (node (ref "R19") (pin "2") (pinfunction "2_2") (pintype "input"))
      (node (ref "U1") (pin "29") (pinfunction "PC6(RESET#/PCINT14)_29") (pintype "unspecified"))
    )
    (net (code "41") (name "RX") (class "Default")
      (node (ref "RX") (pin "1") (pinfunction "1_1") (pintype "unspecified"))
      (node (ref "U1") (pin "31") (pinfunction "PD1(TXD/PCINT17)_31") (pintype "unspecified"))
    )
    (net (code "42") (name "SCL") (class "Default")
      (node (ref "DISPLAY") (pin "3") (pinfunction "3_3") (pintype "unspecified"))
      (node (ref "DISPLAY2") (pin "3") (pinfunction "3_3") (pintype "unspecified"))
      (node (ref "U3") (pin "36") (pinfunction "IO22_36") (pintype "unspecified"))
    )
    (net (code "43") (name "SDA") (class "Default")
      (node (ref "DISPLAY") (pin "4") (pinfunction "4_4") (pintype "unspecified"))
      (node (ref "DISPLAY2") (pin "4") (pinfunction "4_4") (pintype "unspecified"))
      (node (ref "U3") (pin "33") (pinfunction "IO21_33") (pintype "unspecified"))
    )
    (net (code "44") (name "TX") (class "Default")
      (node (ref "TX") (pin "2") (pinfunction "2_2") (pintype "unspecified"))
      (node (ref "U1") (pin "30") (pinfunction "PD0(RXD/PCINT16)_30") (pintype "unspecified"))
    )
    (net (code "45") (name "unconnected-(RJ1-L+-Pad9)") (class "Default")
      (node (ref "RJ1") (pin "9") (pinfunction "L+_9") (pintype "unspecified"))
    )
    (net (code "46") (name "unconnected-(RJ1-L--Pad10)") (class "Default")
      (node (ref "RJ1") (pin "10") (pinfunction "L-_10") (pintype "unspecified"))
    )
    (net (code "47") (name "unconnected-(RJ1-R+-Pad11)") (class "Default")
      (node (ref "RJ1") (pin "11") (pinfunction "R+_11") (pintype "unspecified"))
    )
    (net (code "48") (name "unconnected-(RJ1-R--Pad12)") (class "Default")
      (node (ref "RJ1") (pin "12") (pinfunction "R-_12") (pintype "unspecified"))
    )
    (net (code "49") (name "unconnected-(RJ2-L+-Pad9)") (class "Default")
      (node (ref "RJ2") (pin "9") (pinfunction "L+_9") (pintype "unspecified"))
    )
    (net (code "50") (name "unconnected-(RJ2-L--Pad10)") (class "Default")
      (node (ref "RJ2") (pin "10") (pinfunction "L-_10") (pintype "unspecified"))
    )
    (net (code "51") (name "unconnected-(RJ2-R+-Pad11)") (class "Default")
      (node (ref "RJ2") (pin "11") (pinfunction "R+_11") (pintype "unspecified"))
    )
    (net (code "52") (name "unconnected-(RJ2-R--Pad12)") (class "Default")
      (node (ref "RJ2") (pin "12") (pinfunction "R-_12") (pintype "unspecified"))
    )
    (net (code "53") (name "unconnected-(SW1-Pad2)") (class "Default")
      (node (ref "SW1") (pin "2") (pinfunction "2_2") (pintype "unspecified"))
    )
    (net (code "54") (name "unconnected-(SW1-Pad3)") (class "Default")
      (node (ref "SW1") (pin "3") (pinfunction "3_3") (pintype "unspecified"))
    )
    (net (code "55") (name "unconnected-(U1-(PCINT0{slash}CLKO{slash}ICP1)PB0-Pad12)") (class "Default")
      (node (ref "U1") (pin "12") (pinfunction "(PCINT0/CLKO/ICP1)PB0_12") (pintype "unspecified"))
    )
    (net (code "56") (name "unconnected-(U1-(PCINT1{slash}OC1A)PB1-Pad13)") (class "Default")
      (node (ref "U1") (pin "13") (pinfunction "(PCINT1/OC1A)PB1_13") (pintype "unspecified"))
    )
    (net (code "57") (name "unconnected-(U1-(PCINT2{slash}SS#{slash}OC1B)PB2-Pad14)") (class "Default")
      (node (ref "U1") (pin "14") (pinfunction "(PCINT2/SS#/OC1B)PB2_14") (pintype "unspecified"))
    )
    (net (code "58") (name "unconnected-(U1-(PCINT3{slash}OC2A{slash}MOSI)PB3-Pad15)") (class "Default")
      (node (ref "U1") (pin "15") (pinfunction "(PCINT3/OC2A/MOSI)PB3_15") (pintype "unspecified"))
    )
    (net (code "59") (name "unconnected-(U1-(PCINT4{slash}MISO)PB4-Pad16)") (class "Default")
      (node (ref "U1") (pin "16") (pinfunction "(PCINT4/MISO)PB4_16") (pintype "unspecified"))
    )
    (net (code "60") (name "unconnected-(U1-(PCINT6{slash}XTAL1{slash}TOSC1)PB6-Pad7)") (class "Default")
      (node (ref "U1") (pin "7") (pinfunction "(PCINT6/XTAL1/TOSC1)PB6_7") (pintype "unspecified"))
    )
    (net (code "61") (name "unconnected-(U1-(PCINT7{slash}XTAL2{slash}TOSC2)PB7-Pad8)") (class "Default")
      (node (ref "U1") (pin "8") (pinfunction "(PCINT7/XTAL2/TOSC2)PB7_8") (pintype "unspecified"))
    )
    (net (code "62") (name "unconnected-(U1-(PCINT19{slash}OC2B{slash}INT1)PD3-Pad1)") (class "Default")
      (node (ref "U1") (pin "1") (pinfunction "(PCINT19/OC2B/INT1)PD3_1") (pintype "unspecified"))
    )
    (net (code "63") (name "unconnected-(U1-(PCINT20{slash}XCK{slash}T0)PD4-Pad2)") (class "Default")
      (node (ref "U1") (pin "2") (pinfunction "(PCINT20/XCK/T0)PD4_2") (pintype "unspecified"))
    )
    (net (code "64") (name "unconnected-(U1-(PCINT21{slash}OC0B{slash}T1)PD5-Pad9)") (class "Default")
      (node (ref "U1") (pin "9") (pinfunction "(PCINT21/OC0B/T1)PD5_9") (pintype "unspecified"))
    )
    (net (code "65") (name "unconnected-(U1-(PCINT22{slash}OC0A{slash}AIN0)PD6-Pad10)") (class "Default")
      (node (ref "U1") (pin "10") (pinfunction "(PCINT22/OC0A/AIN0)PD6_10") (pintype "unspecified"))
    )
    (net (code "66") (name "unconnected-(U1-(PCINT23{slash}AIN1)PD7-Pad11)") (class "Default")
      (node (ref "U1") (pin "11") (pinfunction "(PCINT23/AIN1)PD7_11") (pintype "unspecified"))
    )
    (net (code "67") (name "unconnected-(U1-AREF-Pad20)") (class "Default")
      (node (ref "U1") (pin "20") (pinfunction "AREF_20") (pintype "unspecified"))
    )
    (net (code "68") (name "unconnected-(U1-PB5(SCK{slash}PCINT5)-Pad17)") (class "Default")
      (node (ref "U1") (pin "17") (pinfunction "PB5(SCK/PCINT5)_17") (pintype "unspecified"))
    )
    (net (code "69") (name "unconnected-(U1-PD2(INT0{slash}PCINT18)-Pad32)") (class "Default")
      (node (ref "U1") (pin "32") (pinfunction "PD2(INT0/PCINT18)_32") (pintype "unspecified"))
    )
    (net (code "70") (name "unconnected-(U3-CLK-Pad20)") (class "Default")
      (node (ref "U3") (pin "20") (pinfunction "CLK_20") (pintype "unspecified"))
    )
    (net (code "71") (name "unconnected-(U3-CMD-Pad19)") (class "Default")
      (node (ref "U3") (pin "19") (pinfunction "CMD_19") (pintype "unspecified"))
    )
    (net (code "72") (name "unconnected-(U3-IO2-Pad24)") (class "Default")
      (node (ref "U3") (pin "24") (pinfunction "IO2_24") (pintype "unspecified"))
    )
    (net (code "73") (name "unconnected-(U3-IO5-Pad29)") (class "Default")
      (node (ref "U3") (pin "29") (pinfunction "IO5_29") (pintype "unspecified"))
    )
    (net (code "74") (name "unconnected-(U3-IO12-Pad14)") (class "Default")
      (node (ref "U3") (pin "14") (pinfunction "IO12_14") (pintype "unspecified"))
    )
    (net (code "75") (name "unconnected-(U3-IO13-Pad16)") (class "Default")
      (node (ref "U3") (pin "16") (pinfunction "IO13_16") (pintype "unspecified"))
    )
    (net (code "76") (name "unconnected-(U3-IO14-Pad13)") (class "Default")
      (node (ref "U3") (pin "13") (pinfunction "IO14_13") (pintype "unspecified"))
    )
    (net (code "77") (name "unconnected-(U3-IO15-Pad23)") (class "Default")
      (node (ref "U3") (pin "23") (pinfunction "IO15_23") (pintype "unspecified"))
    )
    (net (code "78") (name "unconnected-(U3-IO16-Pad27)") (class "Default")
      (node (ref "U3") (pin "27") (pinfunction "IO16_27") (pintype "unspecified"))
    )
    (net (code "79") (name "unconnected-(U3-IO17-Pad28)") (class "Default")
      (node (ref "U3") (pin "28") (pinfunction "IO17_28") (pintype "unspecified"))
    )
    (net (code "80") (name "unconnected-(U3-IO18-Pad30)") (class "Default")
      (node (ref "U3") (pin "30") (pinfunction "IO18_30") (pintype "unspecified"))
    )
    (net (code "81") (name "unconnected-(U3-IO19-Pad31)") (class "Default")
      (node (ref "U3") (pin "31") (pinfunction "IO19_31") (pintype "unspecified"))
    )
    (net (code "82") (name "unconnected-(U3-IO23-Pad37)") (class "Default")
      (node (ref "U3") (pin "37") (pinfunction "IO23_37") (pintype "unspecified"))
    )
    (net (code "83") (name "unconnected-(U3-IO34-Pad6)") (class "Default")
      (node (ref "U3") (pin "6") (pinfunction "IO34_6") (pintype "unspecified"))
    )
    (net (code "84") (name "unconnected-(U3-IO35-Pad7)") (class "Default")
      (node (ref "U3") (pin "7") (pinfunction "IO35_7") (pintype "unspecified"))
    )
    (net (code "85") (name "unconnected-(U3-NC-Pad32)") (class "Default")
      (node (ref "U3") (pin "32") (pinfunction "NC_32") (pintype "unspecified"))
    )
    (net (code "86") (name "unconnected-(U3-SD0-Pad21)") (class "Default")
      (node (ref "U3") (pin "21") (pinfunction "SD0_21") (pintype "unspecified"))
    )
    (net (code "87") (name "unconnected-(U3-SD1-Pad22)") (class "Default")
      (node (ref "U3") (pin "22") (pinfunction "SD1_22") (pintype "unspecified"))
    )
    (net (code "88") (name "unconnected-(U3-SD2-Pad17)") (class "Default")
      (node (ref "U3") (pin "17") (pinfunction "SD2_17") (pintype "unspecified"))
    )
    (net (code "89") (name "unconnected-(U3-SD3-Pad18)") (class "Default")
      (node (ref "U3") (pin "18") (pinfunction "SD3_18") (pintype "unspecified"))
    )
    (net (code "90") (name "unconnected-(U3-SENSOR_VN-Pad5)") (class "Default")
      (node (ref "U3") (pin "5") (pinfunction "SENSOR_VN_5") (pintype "unspecified"))
    )
    (net (code "91") (name "unconnected-(U3-SENSOR_VP-Pad4)") (class "Default")
      (node (ref "U3") (pin "4") (pinfunction "SENSOR_VP_4") (pintype "unspecified"))
    )
    (net (code "92") (name "unconnected-(USB1-CC1-PadA5)") (class "Default")
      (node (ref "USB1") (pin "A5") (pinfunction "CC1_A5") (pintype "unspecified"))
    )
    (net (code "93") (name "unconnected-(USB1-CC2-PadB5)") (class "Default")
      (node (ref "USB1") (pin "B5") (pinfunction "CC2_B5") (pintype "unspecified"))
    )
    (net (code "94") (name "unconnected-(USB1-DN1-PadA7)") (class "Default")
      (node (ref "USB1") (pin "A7") (pinfunction "DN1_A7") (pintype "unspecified"))
    )
    (net (code "95") (name "unconnected-(USB1-DN2-PadB7)") (class "Default")
      (node (ref "USB1") (pin "B7") (pinfunction "DN2_B7") (pintype "unspecified"))
    )
    (net (code "96") (name "unconnected-(USB1-DP1-PadA6)") (class "Default")
      (node (ref "USB1") (pin "A6") (pinfunction "DP1_A6") (pintype "unspecified"))
    )
    (net (code "97") (name "unconnected-(USB1-DP2-PadB6)") (class "Default")
      (node (ref "USB1") (pin "B6") (pinfunction "DP2_B6") (pintype "unspecified"))
    )
    (net (code "98") (name "unconnected-(USB1-EP-Pad1)") (class "Default")
      (node (ref "USB1") (pin "1") (pinfunction "EP_1") (pintype "unspecified"))
    )
    (net (code "99") (name "unconnected-(USB1-EP-Pad2)") (class "Default")
      (node (ref "USB1") (pin "2") (pinfunction "EP_2") (pintype "unspecified"))
    )
    (net (code "100") (name "unconnected-(USB1-EP-Pad3)") (class "Default")
      (node (ref "USB1") (pin "3") (pinfunction "EP_3") (pintype "unspecified"))
    )
    (net (code "101") (name "unconnected-(USB1-EP-Pad4)") (class "Default")
      (node (ref "USB1") (pin "4") (pinfunction "EP_4") (pintype "unspecified"))
    )
    (net (code "102") (name "unconnected-(USB1-SUB1-PadA8)") (class "Default")
      (node (ref "USB1") (pin "A8") (pinfunction "SUB1_A8") (pintype "unspecified"))
    )
    (net (code "103") (name "unconnected-(USB1-SUB2-PadB8)") (class "Default")
      (node (ref "USB1") (pin "B8") (pinfunction "SUB2_B8") (pintype "unspecified"))
    )
  )
)
